# Capstone.net
KiCad netlist of a schematic drawn in Altium Designer
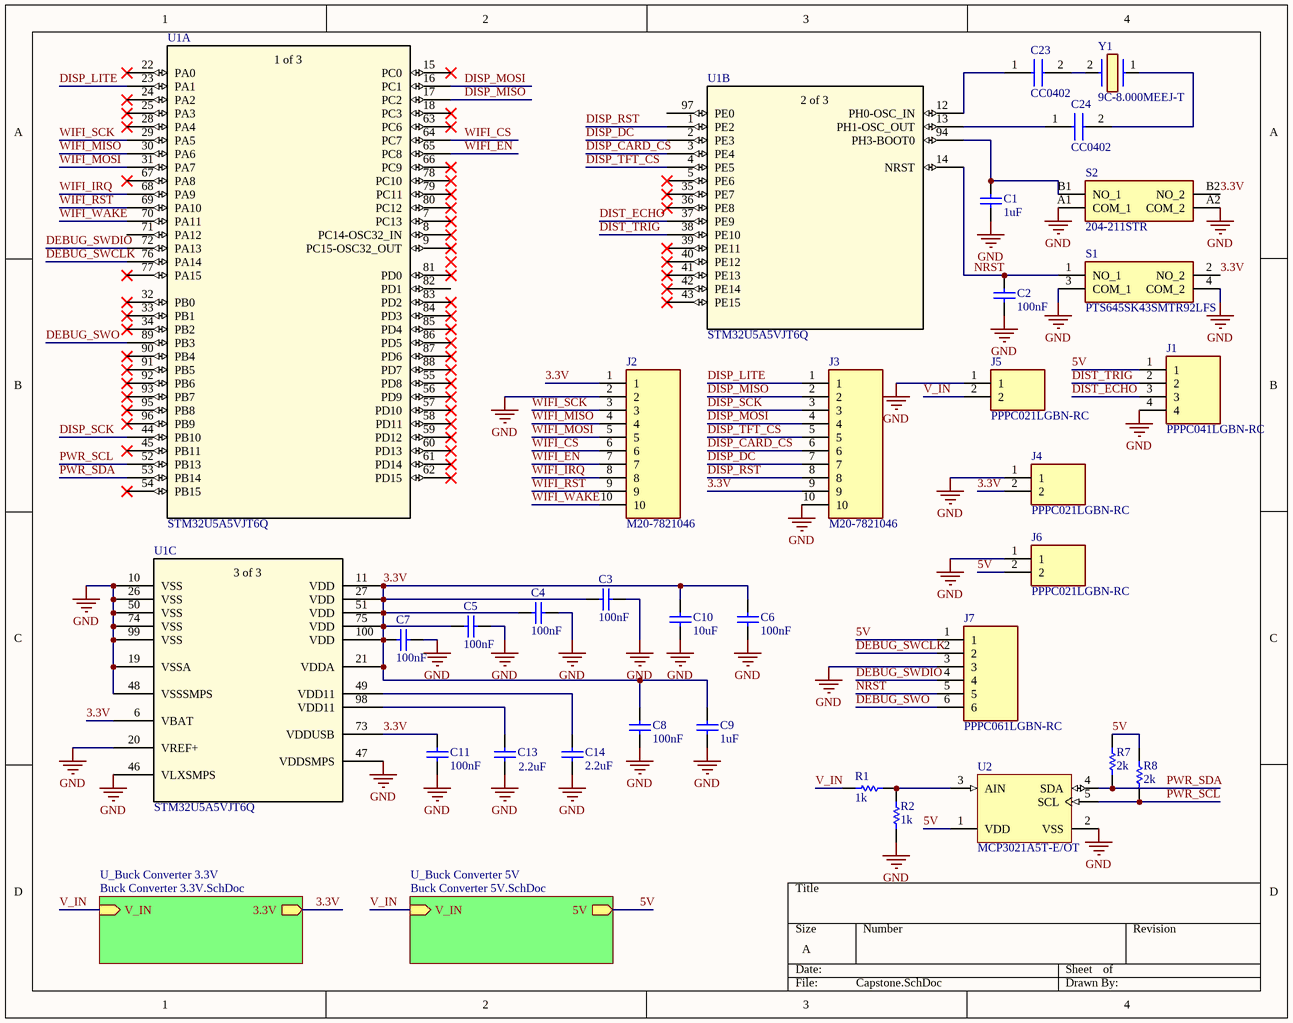
[diagram p0: Capstone.SchDoc]

(export (version "E")
  (design (tool "Eeschema 10.0.6"))
  (components
    (comp (ref "C1")
      (value "1uF")
      (footprint "CAPC2013X135X45LL10T25")
      (description "Chip Capacitor, 4.7 uF, +/- 10%, 16 V, -55 to 85 degC, 0805 (2012 Metric), RoHS, Tape and Reel")
      (fields (field (name "TOLERANCE") "10%") (field (name "PARTNUMBER") "GRM21BR61C475KA88L"))
      (libsource (lib "Altium Content Vault") (part "CAP-NP-2"))
    )
    (comp (ref "C2")
      (value "100nF")
      (footprint "CAPC2013X135X45LL10T25")
      (description "Chip Capacitor, 4.7 uF, +/- 10%, 16 V, -55 to 85 degC, 0805 (2012 Metric), RoHS, Tape and Reel")
      (fields (field (name "TOLERANCE") "10%") (field (name "PARTNUMBER") "GRM21BR61C475KA88L"))
      (libsource (lib "Altium Content Vault") (part "CAP-NP-2"))
    )
    (comp (ref "C3")
      (value "100nF")
      (footprint "CAPC2013X135X45LL10T25")
      (description "Chip Capacitor, 4.7 uF, +/- 10%, 16 V, -55 to 85 degC, 0805 (2012 Metric), RoHS, Tape and Reel")
      (fields (field (name "TOLERANCE") "10%") (field (name "PARTNUMBER") "GRM21BR61C475KA88L"))
      (libsource (lib "Altium Content Vault") (part "CAP-NP-2"))
    )
    (comp (ref "C4")
      (value "100nF")
      (footprint "CAPC2013X135X45LL10T25")
      (description "Chip Capacitor, 4.7 uF, +/- 10%, 16 V, -55 to 85 degC, 0805 (2012 Metric), RoHS, Tape and Reel")
      (fields (field (name "TOLERANCE") "10%") (field (name "PARTNUMBER") "GRM21BR61C475KA88L"))
      (libsource (lib "Altium Content Vault") (part "CAP-NP-2"))
    )
    (comp (ref "C5")
      (value "100nF")
      (footprint "CAPC2013X135X45LL10T25")
      (description "Chip Capacitor, 4.7 uF, +/- 10%, 16 V, -55 to 85 degC, 0805 (2012 Metric), RoHS, Tape and Reel")
      (fields (field (name "TOLERANCE") "10%") (field (name "PARTNUMBER") "GRM21BR61C475KA88L"))
      (libsource (lib "Altium Content Vault") (part "CAP-NP-2"))
    )
    (comp (ref "C6")
      (value "100nF")
      (footprint "CAPC2013X135X45LL10T25")
      (description "Chip Capacitor, 4.7 uF, +/- 10%, 16 V, -55 to 85 degC, 0805 (2012 Metric), RoHS, Tape and Reel")
      (fields (field (name "TOLERANCE") "10%") (field (name "PARTNUMBER") "GRM21BR61C475KA88L"))
      (libsource (lib "Altium Content Vault") (part "CAP-NP-2"))
    )
    (comp (ref "C7")
      (value "100nF")
      (footprint "CAPC2013X135X45LL10T25")
      (description "Chip Capacitor, 4.7 uF, +/- 10%, 16 V, -55 to 85 degC, 0805 (2012 Metric), RoHS, Tape and Reel")
      (fields (field (name "TOLERANCE") "10%") (field (name "PARTNUMBER") "GRM21BR61C475KA88L"))
      (libsource (lib "Altium Content Vault") (part "CAP-NP-2"))
    )
    (comp (ref "C8")
      (value "100nF")
      (footprint "CAPC2013X135X45LL10T25")
      (description "Chip Capacitor, 4.7 uF, +/- 10%, 16 V, -55 to 85 degC, 0805 (2012 Metric), RoHS, Tape and Reel")
      (fields (field (name "TOLERANCE") "10%") (field (name "PARTNUMBER") "GRM21BR61C475KA88L"))
      (libsource (lib "Altium Content Vault") (part "CAP-NP-2"))
    )
    (comp (ref "C9")
      (value "1uF")
      (footprint "CAPC2013X135X45LL10T25")
      (description "Chip Capacitor, 4.7 uF, +/- 10%, 16 V, -55 to 85 degC, 0805 (2012 Metric), RoHS, Tape and Reel")
      (fields (field (name "TOLERANCE") "10%") (field (name "PARTNUMBER") "GRM21BR61C475KA88L"))
      (libsource (lib "Altium Content Vault") (part "CAP-NP-2"))
    )
    (comp (ref "C10")
      (value "10uF")
      (footprint "CAPC2013X135X45LL10T25")
      (description "Chip Capacitor, 4.7 uF, +/- 10%, 16 V, -55 to 85 degC, 0805 (2012 Metric), RoHS, Tape and Reel")
      (fields (field (name "TOLERANCE") "10%") (field (name "PARTNUMBER") "GRM21BR61C475KA88L"))
      (libsource (lib "Altium Content Vault") (part "CAP-NP-2"))
    )
    (comp (ref "C11")
      (value "100nF")
      (footprint "CAPC2013X135X45LL10T25")
      (description "Chip Capacitor, 4.7 uF, +/- 10%, 16 V, -55 to 85 degC, 0805 (2012 Metric), RoHS, Tape and Reel")
      (fields (field (name "TOLERANCE") "10%") (field (name "PARTNUMBER") "GRM21BR61C475KA88L"))
      (libsource (lib "Altium Content Vault") (part "CAP-NP-2"))
    )
    (comp (ref "C13")
      (value "2.2uF")
      (footprint "CAPC2013X135X45LL10T25")
      (description "Chip Capacitor, 4.7 uF, +/- 10%, 16 V, -55 to 85 degC, 0805 (2012 Metric), RoHS, Tape and Reel")
      (fields (field (name "TOLERANCE") "10%") (field (name "PARTNUMBER") "GRM21BR61C475KA88L"))
      (libsource (lib "Altium Content Vault") (part "CAP-NP-2"))
    )
    (comp (ref "C14")
      (value "2.2uF")
      (footprint "CAPC2013X135X45LL10T25")
      (description "Chip Capacitor, 4.7 uF, +/- 10%, 16 V, -55 to 85 degC, 0805 (2012 Metric), RoHS, Tape and Reel")
      (fields (field (name "TOLERANCE") "10%") (field (name "PARTNUMBER") "GRM21BR61C475KA88L"))
      (libsource (lib "Altium Content Vault") (part "CAP-NP-2"))
    )
    (comp (ref "C23")
      (value "CC0402")
      (footprint "SamacSys:CAPC1005X55N")
      (description "Capacitor")
      (fields (field (name "MANUFACTURER_PART_NUMBER") "CC0402FRNPO9BN180"))
      (libsource (lib "*") (part "CC0402FRNPO9BN180"))
    )
    (comp (ref "C24")
      (value "CC0402")
      (footprint "SamacSys:CAPC1005X55N")
      (description "Capacitor")
      (fields (field (name "MANUFACTURER_PART_NUMBER") "CC0402FRNPO9BN180"))
      (libsource (lib "*") (part "CC0402FRNPO9BN180"))
    )
    (comp (ref "J1")
      (value "PPPC041LGBN-RC")
      (footprint "PPP4:RHDRRA4W60P0X254_1X4_1066X850X274P")
      (description "Connector")
      (libsource (lib "PPP4") (part "PPPC041LGBN-RC"))
    )
    (comp (ref "J2")
      (value "M20-7821046")
      (footprint "RHDR10W70P0X254_1X10_2580X250X865P")
      (description "Connector")
      (fields (field (name "MOUSER PART NUMBER") "855-M20-7821046"))
      (libsource (lib "8-Pin") (part "M20-7821046"))
    )
    (comp (ref "J3")
      (value "M20-7821046")
      (footprint "RHDR10W70P0X254_1X10_2580X250X865P")
      (description "Connector")
      (fields (field (name "MOUSER PART NUMBER") "855-M20-7821046"))
      (libsource (lib "8-Pin") (part "M20-7821046"))
    )
    (comp (ref "J4")
      (value "PPPC021LGBN-RC")
      (footprint "SamacSys:RHDRRA2W60P0X254_1X2_558X850X274P")
      (description "Connector")
      (libsource (lib "*") (part "PPPC021LGBN-RC"))
    )
    (comp (ref "J5")
      (value "PPPC021LGBN-RC")
      (footprint "SamacSys:RHDRRA2W60P0X254_1X2_558X850X274P")
      (description "Connector")
      (libsource (lib "*") (part "PPPC021LGBN-RC"))
    )
    (comp (ref "J6")
      (value "PPPC021LGBN-RC")
      (footprint "SamacSys:RHDRRA2W60P0X254_1X2_558X850X274P")
      (description "Connector")
      (libsource (lib "*") (part "PPPC021LGBN-RC"))
    )
    (comp (ref "J7")
      (value "PPPC061LGBN-RC")
      (footprint "SamacSys:PPPC061LGBNRC")
      (description "Connector")
      (libsource (lib "*") (part "PPPC061LGBN-RC"))
    )
    (comp (ref "R1")
      (value "1k")
      (footprint "RESC1608X55X25ML10T15")
      (description "Chip Resistor, 0 Ohm, +/- 5%, 0.1 W, -55 to 155 degC, 0603 (1608 Metric), RoHS, Tape and Reel")
      (fields (field (name "TOLERANCE") "5%") (field (name "MANUFACTURER") "Yageo"))
      (libsource (lib "Altium Content Vault") (part "RES-2"))
    )
    (comp (ref "R2")
      (value "1k")
      (footprint "RESC1608X55X25ML10T15")
      (description "Chip Resistor, 0 Ohm, +/- 5%, 0.1 W, -55 to 155 degC, 0603 (1608 Metric), RoHS, Tape and Reel")
      (fields (field (name "TOLERANCE") "5%") (field (name "MANUFACTURER") "Yageo"))
      (libsource (lib "Altium Content Vault") (part "RES-2"))
    )
    (comp (ref "R7")
      (value "2k")
      (footprint "RESC1608X55X25ML10T15")
      (description "Chip Resistor, 0 Ohm, +/- 5%, 0.1 W, -55 to 155 degC, 0603 (1608 Metric), RoHS, Tape and Reel")
      (fields (field (name "TOLERANCE") "5%") (field (name "MANUFACTURER") "Yageo"))
      (libsource (lib "Altium Content Vault") (part "RES-2"))
    )
    (comp (ref "R8")
      (value "2k")
      (footprint "RESC1608X55X25ML10T15")
      (description "Chip Resistor, 0 Ohm, +/- 5%, 0.1 W, -55 to 155 degC, 0603 (1608 Metric), RoHS, Tape and Reel")
      (fields (field (name "TOLERANCE") "5%") (field (name "MANUFACTURER") "Yageo"))
      (libsource (lib "Altium Content Vault") (part "RES-2"))
    )
    (comp (ref "S1")
      (value "PTS645SK43SMTR92LFS")
      (footprint "SamacSys:PTS645SK43SMTR92LFS")
      (description "Switch")
      (fields (field (name "MOUSER PART NUMBER") "611-PTS645SK43SMTR92"))
      (libsource (lib "*") (part "PTS645SK43SMTR92LFS"))
    )
    (comp (ref "S2")
      (value "204-211STR")
      (footprint "SamacSys:204211STR")
      (description "Switch")
      (fields (field (name "MOUSER PART NUMBER") "774-204-211STR"))
      (libsource (lib "*") (part "204-211STR"))
    )
    (comp (ref "U1")
      (value "STM32U5A5VJT6Q")
      (footprint "LQFP-100_STM")
      (description "No Description Available")
      (libsource (lib "STM32U5A5VJT6Q") (part "STM32U5A5VJT6Q"))
    )
    (comp (ref "U2")
      (value "MCP3021A5T-E/OT")
      (footprint "SOT-23-OT5_M")
      (libsource (lib "Altium Content Vault") (part "CON-ADC-MCP3021-5"))
    )
    (comp (ref "Y1")
      (value "9C-8.000MEEJ-T")
      (footprint "SamacSys:9C7680MBBKT")
      (description "Crystal or Oscillator")
      (fields (field (name "MOUSER PART NUMBER") "717-9C-8.000MEEJ-T"))
      (libsource (lib "*") (part "9C-8.000MEEJ-T"))
    )
  )
  (nets
    (net (code "1") (name "/3.3V") (class "Default")
      (node (ref "C10") (pin "2") (pinfunction "2_2") (pintype "passive"))
      (node (ref "C11") (pin "2") (pinfunction "2_2") (pintype "passive"))
      (node (ref "C3") (pin "1") (pinfunction "1_1") (pintype "passive"))
      (node (ref "C4") (pin "1") (pinfunction "1_1") (pintype "passive"))
      (node (ref "C5") (pin "1") (pinfunction "1_1") (pintype "passive"))
      (node (ref "C6") (pin "2") (pinfunction "2_2") (pintype "passive"))
      (node (ref "C7") (pin "1") (pinfunction "1_1") (pintype "passive"))
      (node (ref "C8") (pin "2") (pinfunction "2_2") (pintype "passive"))
      (node (ref "C9") (pin "2") (pinfunction "2_2") (pintype "passive"))
      (node (ref "J2") (pin "1") (pinfunction "1_1") (pintype "passive"))
      (node (ref "J3") (pin "9") (pinfunction "9_9") (pintype "passive"))
      (node (ref "J4") (pin "2") (pinfunction "2_2") (pintype "passive"))
      (node (ref "S1") (pin "2") (pinfunction "NO_2_2") (pintype "passive"))
      (node (ref "S2") (pin "B2") (pinfunction "NO_2_B2") (pintype "passive"))
      (node (ref "U1") (pin "100") (pinfunction "VDD_100") (pintype "power_in"))
      (node (ref "U1") (pin "11") (pinfunction "VDD_11") (pintype "power_in"))
      (node (ref "U1") (pin "21") (pinfunction "VDDA_21") (pintype "power_in"))
      (node (ref "U1") (pin "27") (pinfunction "VDD_27") (pintype "power_in"))
      (node (ref "U1") (pin "51") (pinfunction "VDD_51") (pintype "power_in"))
      (node (ref "U1") (pin "6") (pinfunction "VBAT_6") (pintype "power_in"))
      (node (ref "U1") (pin "73") (pinfunction "VDDUSB_73") (pintype "power_in"))
      (node (ref "U1") (pin "75") (pinfunction "VDD_75") (pintype "power_in"))
    )
    (net (code "2") (name "/5V") (class "Default")
      (node (ref "J1") (pin "1") (pinfunction "1_1") (pintype "passive"))
      (node (ref "J6") (pin "2") (pinfunction "2_2") (pintype "passive"))
      (node (ref "J7") (pin "1") (pinfunction "1_1") (pintype "passive"))
      (node (ref "R7") (pin "1") (pinfunction "1_1") (pintype "passive"))
      (node (ref "R8") (pin "1") (pinfunction "1_1") (pintype "passive"))
      (node (ref "U2") (pin "1") (pinfunction "VDD_1") (pintype "passive"))
    )
    (net (code "4") (name "/DEBUG_SWCLK") (class "Default")
      (node (ref "J7") (pin "2") (pinfunction "2_2") (pintype "passive"))
      (node (ref "U1") (pin "76") (pinfunction "PA14_76") (pintype "bidirectional"))
    )
    (net (code "5") (name "/DEBUG_SWDIO") (class "Default")
      (node (ref "J7") (pin "4") (pinfunction "4_4") (pintype "passive"))
      (node (ref "U1") (pin "72") (pinfunction "PA13_72") (pintype "bidirectional"))
    )
    (net (code "6") (name "/DEBUG_SWO") (class "Default")
      (node (ref "J7") (pin "6") (pinfunction "6_6") (pintype "passive"))
      (node (ref "U1") (pin "89") (pinfunction "PB3_89") (pintype "bidirectional"))
    )
    (net (code "7") (name "/DISP_CARD_CS") (class "Default")
      (node (ref "J3") (pin "6") (pinfunction "6_6") (pintype "passive"))
      (node (ref "U1") (pin "3") (pinfunction "PE4_3") (pintype "bidirectional"))
    )
    (net (code "8") (name "/DISP_DC") (class "Default")
      (node (ref "J3") (pin "7") (pinfunction "7_7") (pintype "passive"))
      (node (ref "U1") (pin "2") (pinfunction "PE3_2") (pintype "bidirectional"))
    )
    (net (code "9") (name "/DISP_LITE") (class "Default")
      (node (ref "J3") (pin "1") (pinfunction "1_1") (pintype "passive"))
      (node (ref "U1") (pin "23") (pinfunction "PA1_23") (pintype "bidirectional"))
    )
    (net (code "10") (name "/DISP_MISO") (class "Default")
      (node (ref "J3") (pin "2") (pinfunction "2_2") (pintype "passive"))
      (node (ref "U1") (pin "17") (pinfunction "PC2_17") (pintype "bidirectional"))
    )
    (net (code "11") (name "/DISP_MOSI") (class "Default")
      (node (ref "J3") (pin "4") (pinfunction "4_4") (pintype "passive"))
      (node (ref "U1") (pin "16") (pinfunction "PC1_16") (pintype "bidirectional"))
    )
    (net (code "12") (name "/DISP_RST") (class "Default")
      (node (ref "J3") (pin "8") (pinfunction "8_8") (pintype "passive"))
      (node (ref "U1") (pin "1") (pinfunction "PE2_1") (pintype "bidirectional"))
    )
    (net (code "13") (name "/DISP_SCK") (class "Default")
      (node (ref "J3") (pin "3") (pinfunction "3_3") (pintype "passive"))
      (node (ref "U1") (pin "44") (pinfunction "PB10_44") (pintype "bidirectional"))
    )
    (net (code "14") (name "/DISP_TFT_CS") (class "Default")
      (node (ref "J3") (pin "5") (pinfunction "5_5") (pintype "passive"))
      (node (ref "U1") (pin "4") (pinfunction "PE5_4") (pintype "bidirectional"))
    )
    (net (code "15") (name "/DIST_ECHO") (class "Default")
      (node (ref "J1") (pin "3") (pinfunction "3_3") (pintype "passive"))
      (node (ref "U1") (pin "37") (pinfunction "PE9_37") (pintype "bidirectional"))
    )
    (net (code "16") (name "/DIST_TRIG") (class "Default")
      (node (ref "J1") (pin "2") (pinfunction "2_2") (pintype "passive"))
      (node (ref "U1") (pin "38") (pinfunction "PE10_38") (pintype "bidirectional"))
    )
    (net (code "17") (name "/NRST") (class "Default")
      (node (ref "C2") (pin "2") (pinfunction "2_2") (pintype "passive"))
      (node (ref "J7") (pin "5") (pinfunction "5_5") (pintype "passive"))
      (node (ref "S1") (pin "1") (pinfunction "NO_1_1") (pintype "passive"))
      (node (ref "U1") (pin "14") (pinfunction "NRST_14") (pintype "bidirectional"))
    )
    (net (code "18") (name "/PWR_SCL") (class "Default")
      (node (ref "R8") (pin "2") (pinfunction "2_2") (pintype "passive"))
      (node (ref "U1") (pin "52") (pinfunction "PB13_52") (pintype "bidirectional"))
      (node (ref "U2") (pin "5") (pinfunction "SCL_5") (pintype "input"))
    )
    (net (code "19") (name "/PWR_SDA") (class "Default")
      (node (ref "R7") (pin "2") (pinfunction "2_2") (pintype "passive"))
      (node (ref "U1") (pin "53") (pinfunction "PB14_53") (pintype "bidirectional"))
      (node (ref "U2") (pin "4") (pinfunction "SDA_4") (pintype "bidirectional"))
    )
    (net (code "20") (name "/V_IN") (class "Default")
      (node (ref "J5") (pin "2") (pinfunction "2_2") (pintype "passive"))
      (node (ref "R1") (pin "2") (pinfunction "2_2") (pintype "passive"))
    )
    (net (code "21") (name "/WIFI_CS") (class "Default")
      (node (ref "J2") (pin "6") (pinfunction "6_6") (pintype "passive"))
      (node (ref "U1") (pin "64") (pinfunction "PC7_64") (pintype "bidirectional"))
    )
    (net (code "22") (name "/WIFI_EN") (class "Default")
      (node (ref "J2") (pin "7") (pinfunction "7_7") (pintype "passive"))
      (node (ref "U1") (pin "65") (pinfunction "PC8_65") (pintype "bidirectional"))
    )
    (net (code "23") (name "/WIFI_IRQ") (class "Default")
      (node (ref "J2") (pin "8") (pinfunction "8_8") (pintype "passive"))
      (node (ref "U1") (pin "68") (pinfunction "PA9_68") (pintype "bidirectional"))
    )
    (net (code "24") (name "/WIFI_MISO") (class "Default")
      (node (ref "J2") (pin "4") (pinfunction "4_4") (pintype "passive"))
      (node (ref "U1") (pin "30") (pinfunction "PA6_30") (pintype "bidirectional"))
    )
    (net (code "25") (name "/WIFI_MOSI") (class "Default")
      (node (ref "J2") (pin "5") (pinfunction "5_5") (pintype "passive"))
      (node (ref "U1") (pin "31") (pinfunction "PA7_31") (pintype "bidirectional"))
    )
    (net (code "26") (name "/WIFI_RST") (class "Default")
      (node (ref "J2") (pin "9") (pinfunction "9_9") (pintype "passive"))
      (node (ref "U1") (pin "69") (pinfunction "PA10_69") (pintype "bidirectional"))
    )
    (net (code "27") (name "/WIFI_SCK") (class "Default")
      (node (ref "J2") (pin "3") (pinfunction "3_3") (pintype "passive"))
      (node (ref "U1") (pin "29") (pinfunction "PA5_29") (pintype "bidirectional"))
    )
    (net (code "28") (name "/WIFI_WAKE") (class "Default")
      (node (ref "J2") (pin "10") (pinfunction "10_10") (pintype "passive"))
      (node (ref "U1") (pin "70") (pinfunction "PA11_70") (pintype "bidirectional"))
    )
    (net (code "29") (name "GND") (class "Default")
      (node (ref "C1") (pin "1") (pinfunction "1_1") (pintype "passive"))
      (node (ref "C10") (pin "1") (pinfunction "1_1") (pintype "passive"))
      (node (ref "C11") (pin "1") (pinfunction "1_1") (pintype "passive"))
      (node (ref "C13") (pin "1") (pinfunction "1_1") (pintype "passive"))
      (node (ref "C14") (pin "1") (pinfunction "1_1") (pintype "passive"))
      (node (ref "C2") (pin "1") (pinfunction "1_1") (pintype "passive"))
      (node (ref "C3") (pin "2") (pinfunction "2_2") (pintype "passive"))
      (node (ref "C4") (pin "2") (pinfunction "2_2") (pintype "passive"))
      (node (ref "C5") (pin "2") (pinfunction "2_2") (pintype "passive"))
      (node (ref "C6") (pin "1") (pinfunction "1_1") (pintype "passive"))
      (node (ref "C7") (pin "2") (pinfunction "2_2") (pintype "passive"))
      (node (ref "C8") (pin "1") (pinfunction "1_1") (pintype "passive"))
      (node (ref "C9") (pin "1") (pinfunction "1_1") (pintype "passive"))
      (node (ref "J1") (pin "4") (pinfunction "4_4") (pintype "passive"))
      (node (ref "J2") (pin "2") (pinfunction "2_2") (pintype "passive"))
      (node (ref "J3") (pin "10") (pinfunction "10_10") (pintype "passive"))
      (node (ref "J4") (pin "1") (pinfunction "1_1") (pintype "passive"))
      (node (ref "J5") (pin "1") (pinfunction "1_1") (pintype "passive"))
      (node (ref "J6") (pin "1") (pinfunction "1_1") (pintype "passive"))
      (node (ref "J7") (pin "3") (pinfunction "3_3") (pintype "passive"))
      (node (ref "R2") (pin "2") (pinfunction "2_2") (pintype "passive"))
      (node (ref "S1") (pin "3") (pinfunction "COM_1_3") (pintype "passive"))
      (node (ref "S1") (pin "4") (pinfunction "COM_2_4") (pintype "passive"))
      (node (ref "S2") (pin "A1") (pinfunction "COM_1_A1") (pintype "passive"))
      (node (ref "S2") (pin "A2") (pinfunction "COM_2_A2") (pintype "passive"))
      (node (ref "U1") (pin "10") (pinfunction "VSS_10") (pintype "power_in"))
      (node (ref "U1") (pin "19") (pinfunction "VSSA_19") (pintype "power_in"))
      (node (ref "U1") (pin "20") (pinfunction "VREF+_20") (pintype "power_in"))
      (node (ref "U1") (pin "26") (pinfunction "VSS_26") (pintype "power_in"))
      (node (ref "U1") (pin "46") (pinfunction "VLXSMPS_46") (pintype "power_in"))
      (node (ref "U1") (pin "47") (pinfunction "VDDSMPS_47") (pintype "power_in"))
      (node (ref "U1") (pin "48") (pinfunction "VSSSMPS_48") (pintype "power_in"))
      (node (ref "U1") (pin "50") (pinfunction "VSS_50") (pintype "power_in"))
      (node (ref "U1") (pin "74") (pinfunction "VSS_74") (pintype "power_in"))
      (node (ref "U1") (pin "99") (pinfunction "VSS_99") (pintype "power_in"))
      (node (ref "U2") (pin "2") (pinfunction "VSS_2") (pintype "passive"))
    )
    (net (code "30") (name "Net-(C13-Pad2)") (class "Default")
      (node (ref "C13") (pin "2") (pinfunction "2_2") (pintype "passive"))
      (node (ref "U1") (pin "98") (pinfunction "VDD11_98") (pintype "power_in"))
    )
    (net (code "31") (name "Net-(C14-Pad2)") (class "Default")
      (node (ref "C14") (pin "2") (pinfunction "2_2") (pintype "passive"))
      (node (ref "U1") (pin "49") (pinfunction "VDD11_49") (pintype "power_in"))
    )
    (net (code "32") (name "Net-(C23-Pad2)") (class "Default")
      (node (ref "C23") (pin "2") (pinfunction "2_2") (pintype "passive"))
      (node (ref "Y1") (pin "2") (pinfunction "2_2") (pintype "passive"))
    )
    (net (code "33") (name "Net-(C24-Pad2)") (class "Default")
      (node (ref "C24") (pin "2") (pinfunction "2_2") (pintype "passive"))
      (node (ref "Y1") (pin "1") (pinfunction "1_1") (pintype "passive"))
    )
    (net (code "34") (name "Net-(S2-NO_1)") (class "Default")
      (node (ref "C1") (pin "2") (pinfunction "2_2") (pintype "passive"))
      (node (ref "S2") (pin "B1") (pinfunction "NO_1_B1") (pintype "passive"))
      (node (ref "U1") (pin "94") (pinfunction "PH3-BOOT0_94") (pintype "bidirectional"))
    )
    (net (code "35") (name "Net-(U1B-PH0-OSC_IN)") (class "Default")
      (node (ref "C23") (pin "1") (pinfunction "1_1") (pintype "passive"))
      (node (ref "U1") (pin "12") (pinfunction "PH0-OSC_IN_12") (pintype "bidirectional"))
    )
    (net (code "36") (name "Net-(U1B-PH1-OSC_OUT)") (class "Default")
      (node (ref "C24") (pin "1") (pinfunction "1_1") (pintype "passive"))
      (node (ref "U1") (pin "13") (pinfunction "PH1-OSC_OUT_13") (pintype "bidirectional"))
    )
    (net (code "37") (name "Net-(U2-AIN)") (class "Default")
      (node (ref "R1") (pin "1") (pinfunction "1_1") (pintype "passive"))
      (node (ref "R2") (pin "1") (pinfunction "1_1") (pintype "passive"))
      (node (ref "U2") (pin "3") (pinfunction "AIN_3") (pintype "input"))
    )
    (net (code "38") (name "unconnected-(U1A-PA0-Pad22)") (class "Default")
      (node (ref "U1") (pin "22") (pinfunction "PA0_22") (pintype "bidirectional+no_connect"))
    )
    (net (code "39") (name "unconnected-(U1A-PA2-Pad24)") (class "Default")
      (node (ref "U1") (pin "24") (pinfunction "PA2_24") (pintype "bidirectional+no_connect"))
    )
    (net (code "40") (name "unconnected-(U1A-PA3-Pad25)") (class "Default")
      (node (ref "U1") (pin "25") (pinfunction "PA3_25") (pintype "bidirectional+no_connect"))
    )
    (net (code "41") (name "unconnected-(U1A-PA4-Pad28)") (class "Default")
      (node (ref "U1") (pin "28") (pinfunction "PA4_28") (pintype "bidirectional+no_connect"))
    )
    (net (code "42") (name "unconnected-(U1A-PA8-Pad67)") (class "Default")
      (node (ref "U1") (pin "67") (pinfunction "PA8_67") (pintype "bidirectional+no_connect"))
    )
    (net (code "43") (name "unconnected-(U1A-PA12-Pad71)") (class "Default")
      (node (ref "U1") (pin "71") (pinfunction "PA12_71") (pintype "bidirectional"))
    )
    (net (code "44") (name "unconnected-(U1A-PA15-Pad77)") (class "Default")
      (node (ref "U1") (pin "77") (pinfunction "PA15_77") (pintype "bidirectional+no_connect"))
    )
    (net (code "45") (name "unconnected-(U1A-PB0-Pad32)") (class "Default")
      (node (ref "U1") (pin "32") (pinfunction "PB0_32") (pintype "bidirectional+no_connect"))
    )
    (net (code "46") (name "unconnected-(U1A-PB1-Pad33)") (class "Default")
      (node (ref "U1") (pin "33") (pinfunction "PB1_33") (pintype "bidirectional+no_connect"))
    )
    (net (code "47") (name "unconnected-(U1A-PB2-Pad34)") (class "Default")
      (node (ref "U1") (pin "34") (pinfunction "PB2_34") (pintype "bidirectional+no_connect"))
    )
    (net (code "48") (name "unconnected-(U1A-PB4-Pad90)") (class "Default")
      (node (ref "U1") (pin "90") (pinfunction "PB4_90") (pintype "bidirectional+no_connect"))
    )
    (net (code "49") (name "unconnected-(U1A-PB5-Pad91)") (class "Default")
      (node (ref "U1") (pin "91") (pinfunction "PB5_91") (pintype "bidirectional+no_connect"))
    )
    (net (code "50") (name "unconnected-(U1A-PB6-Pad92)") (class "Default")
      (node (ref "U1") (pin "92") (pinfunction "PB6_92") (pintype "bidirectional+no_connect"))
    )
    (net (code "51") (name "unconnected-(U1A-PB7-Pad93)") (class "Default")
      (node (ref "U1") (pin "93") (pinfunction "PB7_93") (pintype "bidirectional+no_connect"))
    )
    (net (code "52") (name "unconnected-(U1A-PB8-Pad95)") (class "Default")
      (node (ref "U1") (pin "95") (pinfunction "PB8_95") (pintype "bidirectional+no_connect"))
    )
    (net (code "53") (name "unconnected-(U1A-PB9-Pad96)") (class "Default")
      (node (ref "U1") (pin "96") (pinfunction "PB9_96") (pintype "bidirectional+no_connect"))
    )
    (net (code "54") (name "unconnected-(U1A-PB11-Pad45)") (class "Default")
      (node (ref "U1") (pin "45") (pinfunction "PB11_45") (pintype "bidirectional+no_connect"))
    )
    (net (code "55") (name "unconnected-(U1A-PB15-Pad54)") (class "Default")
      (node (ref "U1") (pin "54") (pinfunction "PB15_54") (pintype "bidirectional+no_connect"))
    )
    (net (code "56") (name "unconnected-(U1A-PC0-Pad15)") (class "Default")
      (node (ref "U1") (pin "15") (pinfunction "PC0_15") (pintype "bidirectional+no_connect"))
    )
    (net (code "57") (name "unconnected-(U1A-PC3-Pad18)") (class "Default")
      (node (ref "U1") (pin "18") (pinfunction "PC3_18") (pintype "bidirectional+no_connect"))
    )
    (net (code "58") (name "unconnected-(U1A-PC6-Pad63)") (class "Default")
      (node (ref "U1") (pin "63") (pinfunction "PC6_63") (pintype "bidirectional+no_connect"))
    )
    (net (code "59") (name "unconnected-(U1A-PC9-Pad66)") (class "Default")
      (node (ref "U1") (pin "66") (pinfunction "PC9_66") (pintype "bidirectional+no_connect"))
    )
    (net (code "60") (name "unconnected-(U1A-PC10-Pad78)") (class "Default")
      (node (ref "U1") (pin "78") (pinfunction "PC10_78") (pintype "bidirectional+no_connect"))
    )
    (net (code "61") (name "unconnected-(U1A-PC11-Pad79)") (class "Default")
      (node (ref "U1") (pin "79") (pinfunction "PC11_79") (pintype "bidirectional+no_connect"))
    )
    (net (code "62") (name "unconnected-(U1A-PC12-Pad80)") (class "Default")
      (node (ref "U1") (pin "80") (pinfunction "PC12_80") (pintype "bidirectional+no_connect"))
    )
    (net (code "63") (name "unconnected-(U1A-PC13-Pad7)") (class "Default")
      (node (ref "U1") (pin "7") (pinfunction "PC13_7") (pintype "bidirectional+no_connect"))
    )
    (net (code "64") (name "unconnected-(U1A-PC14-OSC32_IN-Pad8)") (class "Default")
      (node (ref "U1") (pin "8") (pinfunction "PC14-OSC32_IN_8") (pintype "bidirectional+no_connect"))
    )
    (net (code "65") (name "unconnected-(U1A-PC15-OSC32_OUT-Pad9)") (class "Default")
      (node (ref "U1") (pin "9") (pinfunction "PC15-OSC32_OUT_9") (pintype "bidirectional+no_connect"))
    )
    (net (code "66") (name "unconnected-(U1A-PD0-Pad81)") (class "Default")
      (node (ref "U1") (pin "81") (pinfunction "PD0_81") (pintype "bidirectional+no_connect"))
    )
    (net (code "67") (name "unconnected-(U1A-PD1-Pad82)") (class "Default")
      (node (ref "U1") (pin "82") (pinfunction "PD1_82") (pintype "bidirectional"))
    )
    (net (code "68") (name "unconnected-(U1A-PD2-Pad83)") (class "Default")
      (node (ref "U1") (pin "83") (pinfunction "PD2_83") (pintype "bidirectional+no_connect"))
    )
    (net (code "69") (name "unconnected-(U1A-PD3-Pad84)") (class "Default")
      (node (ref "U1") (pin "84") (pinfunction "PD3_84") (pintype "bidirectional+no_connect"))
    )
    (net (code "70") (name "unconnected-(U1A-PD4-Pad85)") (class "Default")
      (node (ref "U1") (pin "85") (pinfunction "PD4_85") (pintype "bidirectional+no_connect"))
    )
    (net (code "71") (name "unconnected-(U1A-PD5-Pad86)") (class "Default")
      (node (ref "U1") (pin "86") (pinfunction "PD5_86") (pintype "bidirectional+no_connect"))
    )
    (net (code "72") (name "unconnected-(U1A-PD6-Pad87)") (class "Default")
      (node (ref "U1") (pin "87") (pinfunction "PD6_87") (pintype "bidirectional+no_connect"))
    )
    (net (code "73") (name "unconnected-(U1A-PD7-Pad88)") (class "Default")
      (node (ref "U1") (pin "88") (pinfunction "PD7_88") (pintype "bidirectional+no_connect"))
    )
    (net (code "74") (name "unconnected-(U1A-PD8-Pad55)") (class "Default")
      (node (ref "U1") (pin "55") (pinfunction "PD8_55") (pintype "bidirectional+no_connect"))
    )
    (net (code "75") (name "unconnected-(U1A-PD9-Pad56)") (class "Default")
      (node (ref "U1") (pin "56") (pinfunction "PD9_56") (pintype "bidirectional+no_connect"))
    )
    (net (code "76") (name "unconnected-(U1A-PD10-Pad57)") (class "Default")
      (node (ref "U1") (pin "57") (pinfunction "PD10_57") (pintype "bidirectional+no_connect"))
    )
    (net (code "77") (name "unconnected-(U1A-PD11-Pad58)") (class "Default")
      (node (ref "U1") (pin "58") (pinfunction "PD11_58") (pintype "bidirectional+no_connect"))
    )
    (net (code "78") (name "unconnected-(U1A-PD12-Pad59)") (class "Default")
      (node (ref "U1") (pin "59") (pinfunction "PD12_59") (pintype "bidirectional+no_connect"))
    )
    (net (code "79") (name "unconnected-(U1A-PD13-Pad60)") (class "Default")
      (node (ref "U1") (pin "60") (pinfunction "PD13_60") (pintype "bidirectional+no_connect"))
    )
    (net (code "80") (name "unconnected-(U1A-PD14-Pad61)") (class "Default")
      (node (ref "U1") (pin "61") (pinfunction "PD14_61") (pintype "bidirectional+no_connect"))
    )
    (net (code "81") (name "unconnected-(U1A-PD15-Pad62)") (class "Default")
      (node (ref "U1") (pin "62") (pinfunction "PD15_62") (pintype "bidirectional+no_connect"))
    )
    (net (code "82") (name "unconnected-(U1B-PE0-Pad97)") (class "Default")
      (node (ref "U1") (pin "97") (pinfunction "PE0_97") (pintype "bidirectional"))
    )
    (net (code "83") (name "unconnected-(U1B-PE6-Pad5)") (class "Default")
      (node (ref "U1") (pin "5") (pinfunction "PE6_5") (pintype "bidirectional+no_connect"))
    )
    (net (code "84") (name "unconnected-(U1B-PE7-Pad35)") (class "Default")
      (node (ref "U1") (pin "35") (pinfunction "PE7_35") (pintype "bidirectional+no_connect"))
    )
    (net (code "85") (name "unconnected-(U1B-PE8-Pad36)") (class "Default")
      (node (ref "U1") (pin "36") (pinfunction "PE8_36") (pintype "bidirectional+no_connect"))
    )
    (net (code "86") (name "unconnected-(U1B-PE11-Pad39)") (class "Default")
      (node (ref "U1") (pin "39") (pinfunction "PE11_39") (pintype "bidirectional+no_connect"))
    )
    (net (code "87") (name "unconnected-(U1B-PE12-Pad40)") (class "Default")
      (node (ref "U1") (pin "40") (pinfunction "PE12_40") (pintype "bidirectional+no_connect"))
    )
    (net (code "88") (name "unconnected-(U1B-PE13-Pad41)") (class "Default")
      (node (ref "U1") (pin "41") (pinfunction "PE13_41") (pintype "bidirectional+no_connect"))
    )
    (net (code "89") (name "unconnected-(U1B-PE14-Pad42)") (class "Default")
      (node (ref "U1") (pin "42") (pinfunction "PE14_42") (pintype "bidirectional+no_connect"))
    )
    (net (code "90") (name "unconnected-(U1B-PE15-Pad43)") (class "Default")
      (node (ref "U1") (pin "43") (pinfunction "PE15_43") (pintype "bidirectional+no_connect"))
    )
  )
)
